# Active_Probe_Proto2.net
KiCad netlist of a schematic drawn in EAGLE
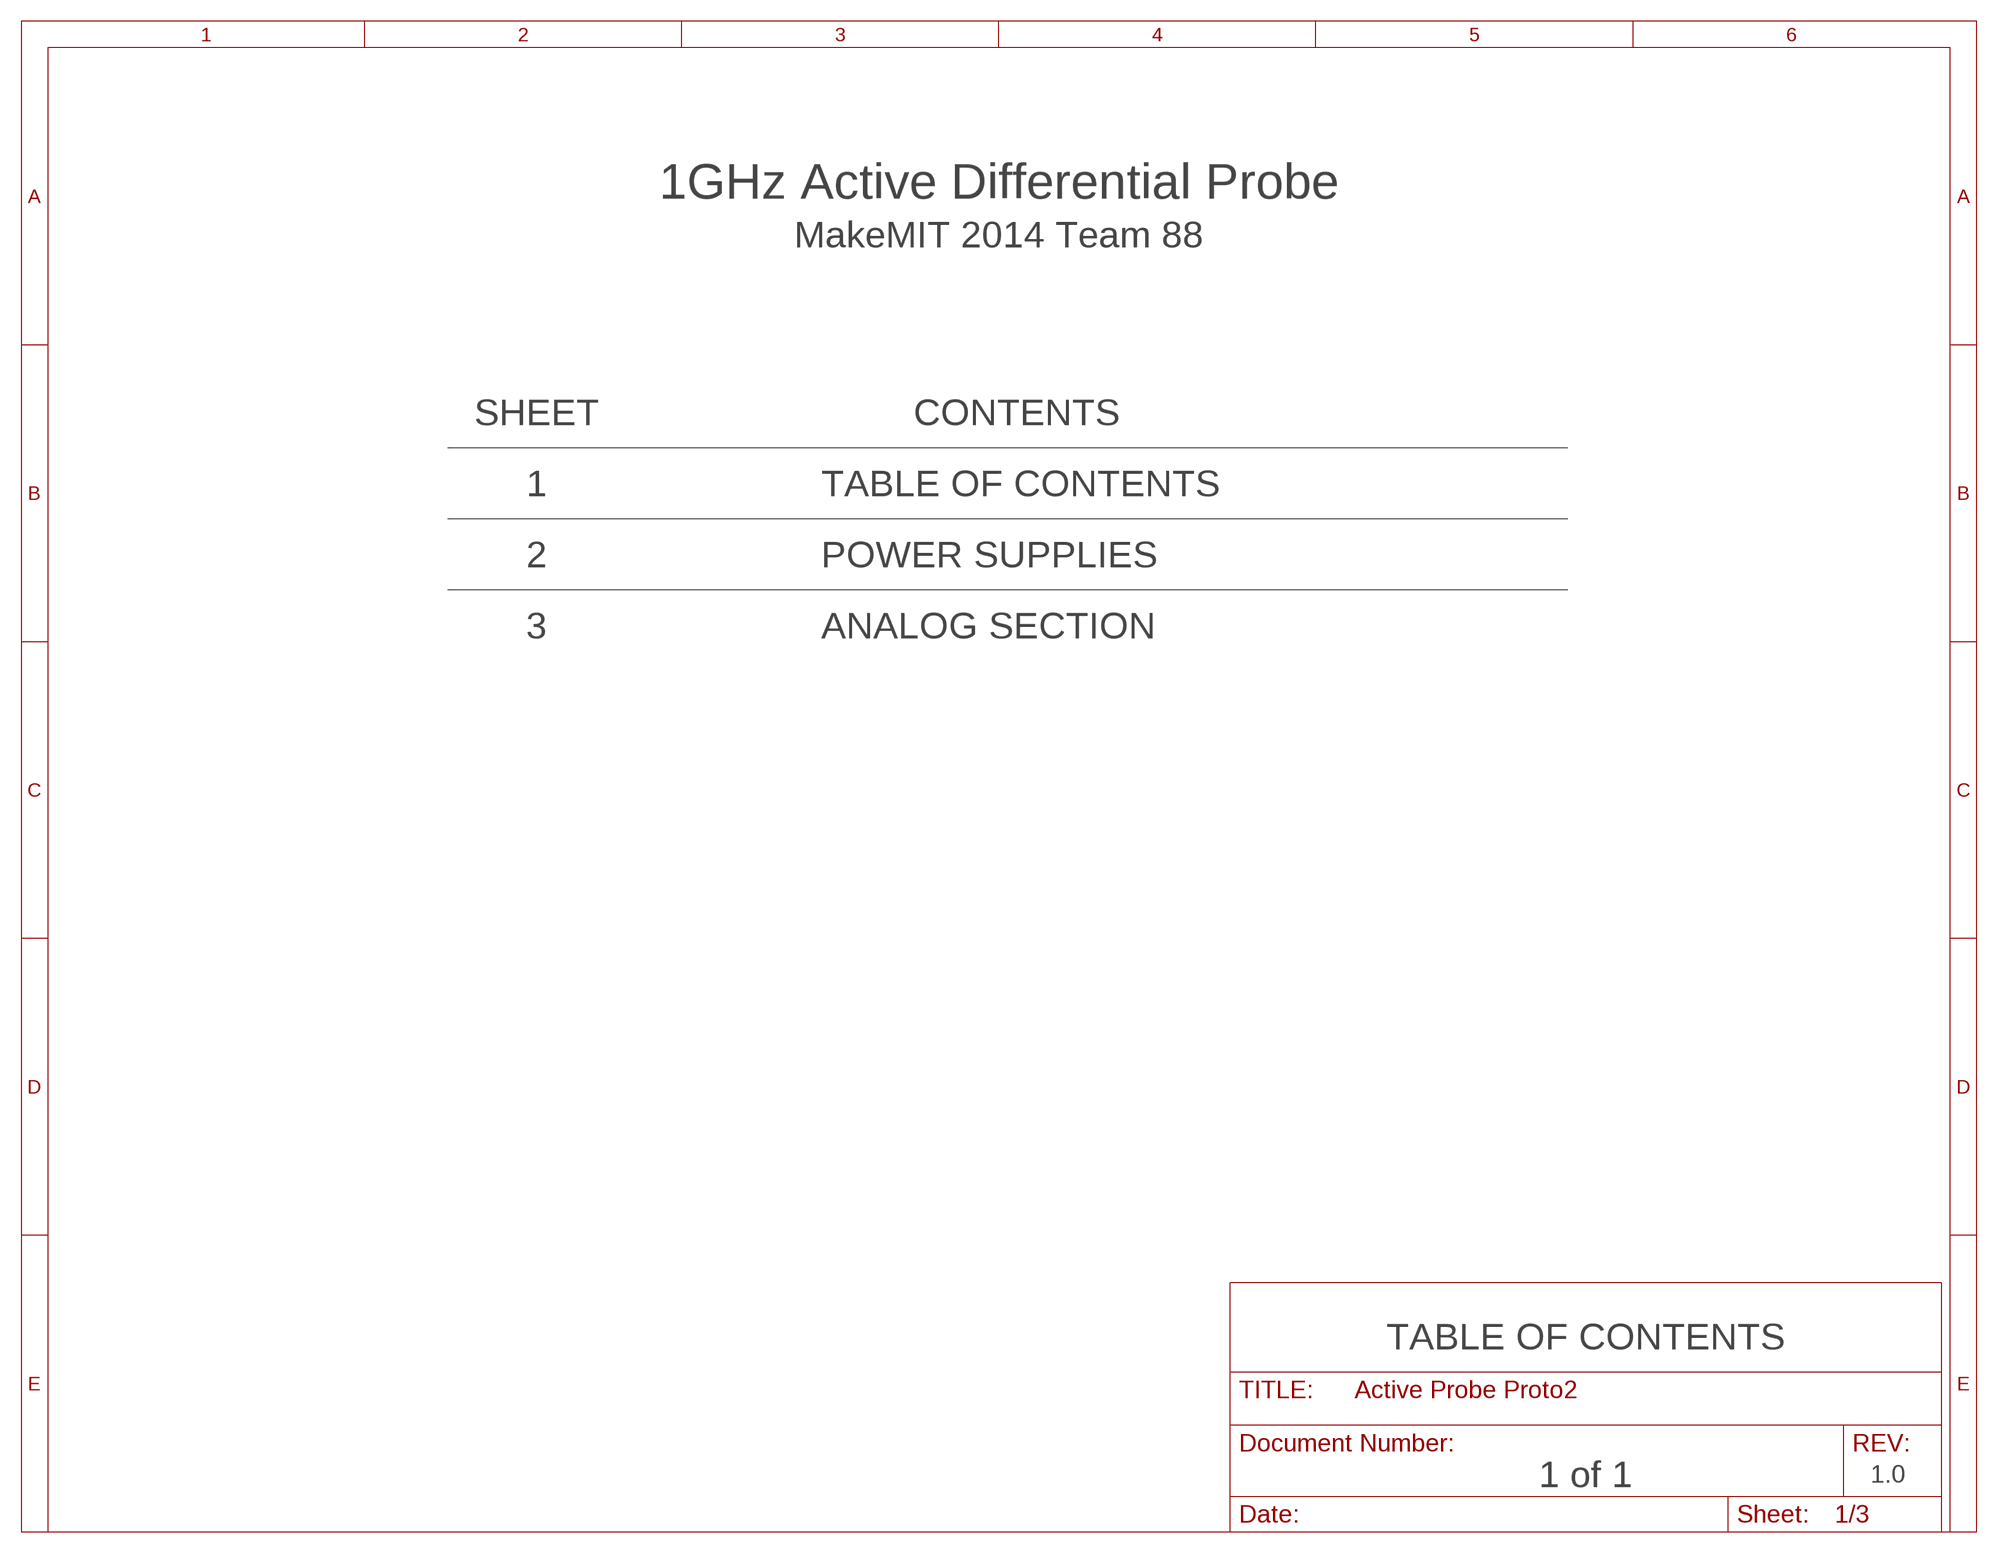
[diagram p0: schematic, sheet 1]
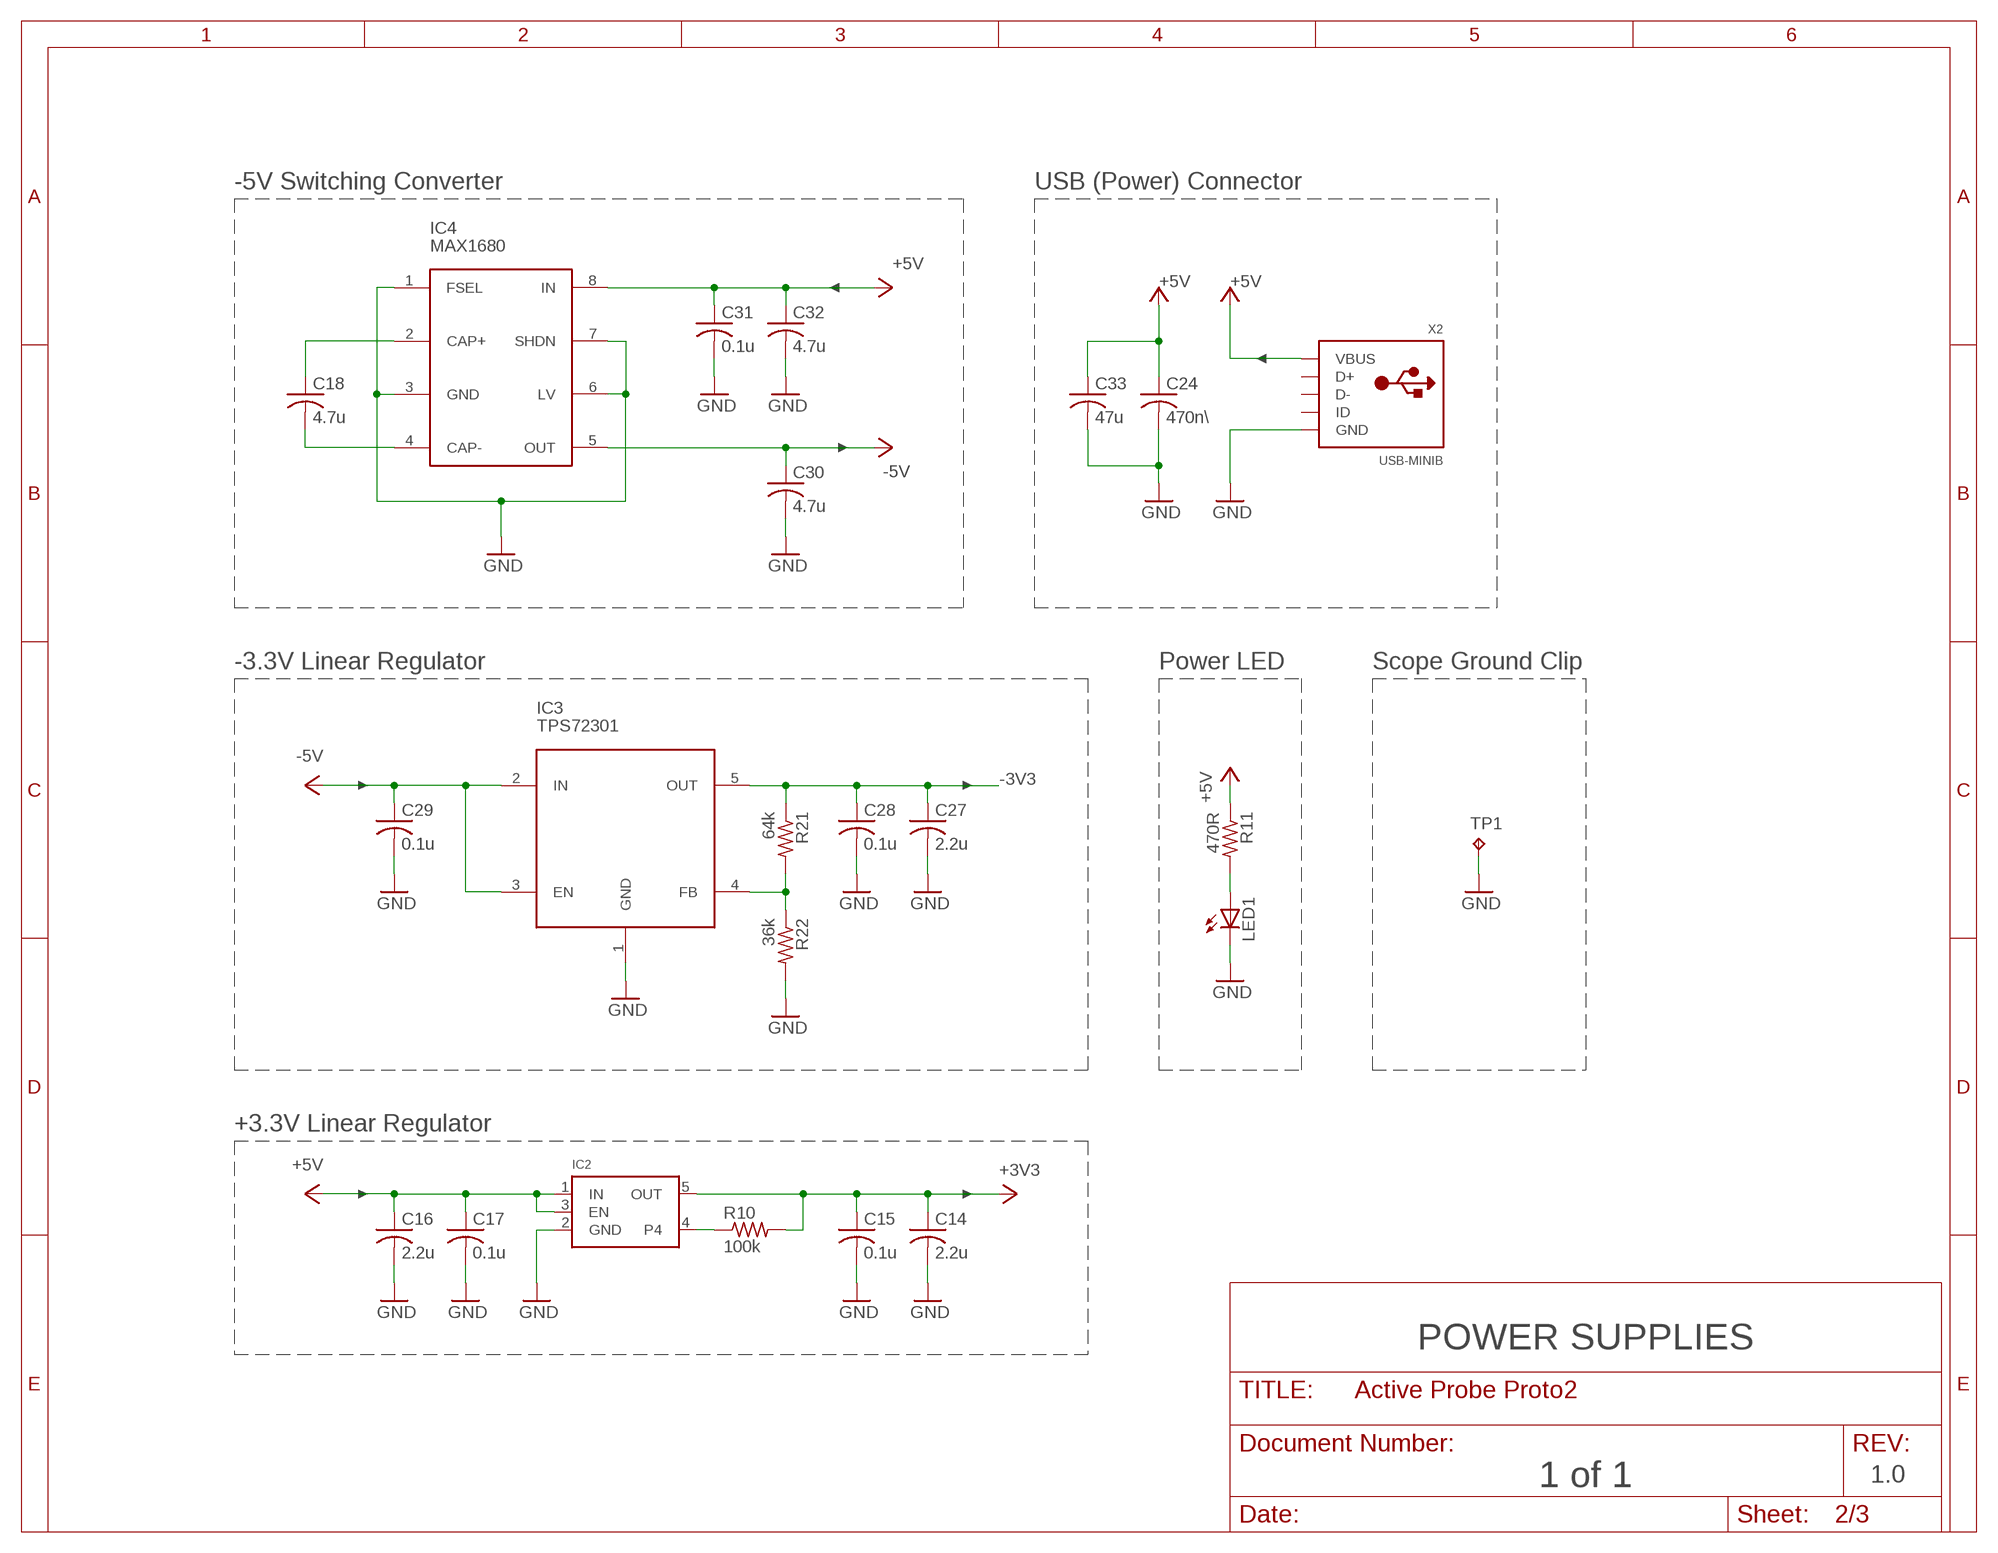
[diagram p1: schematic, sheet 2]
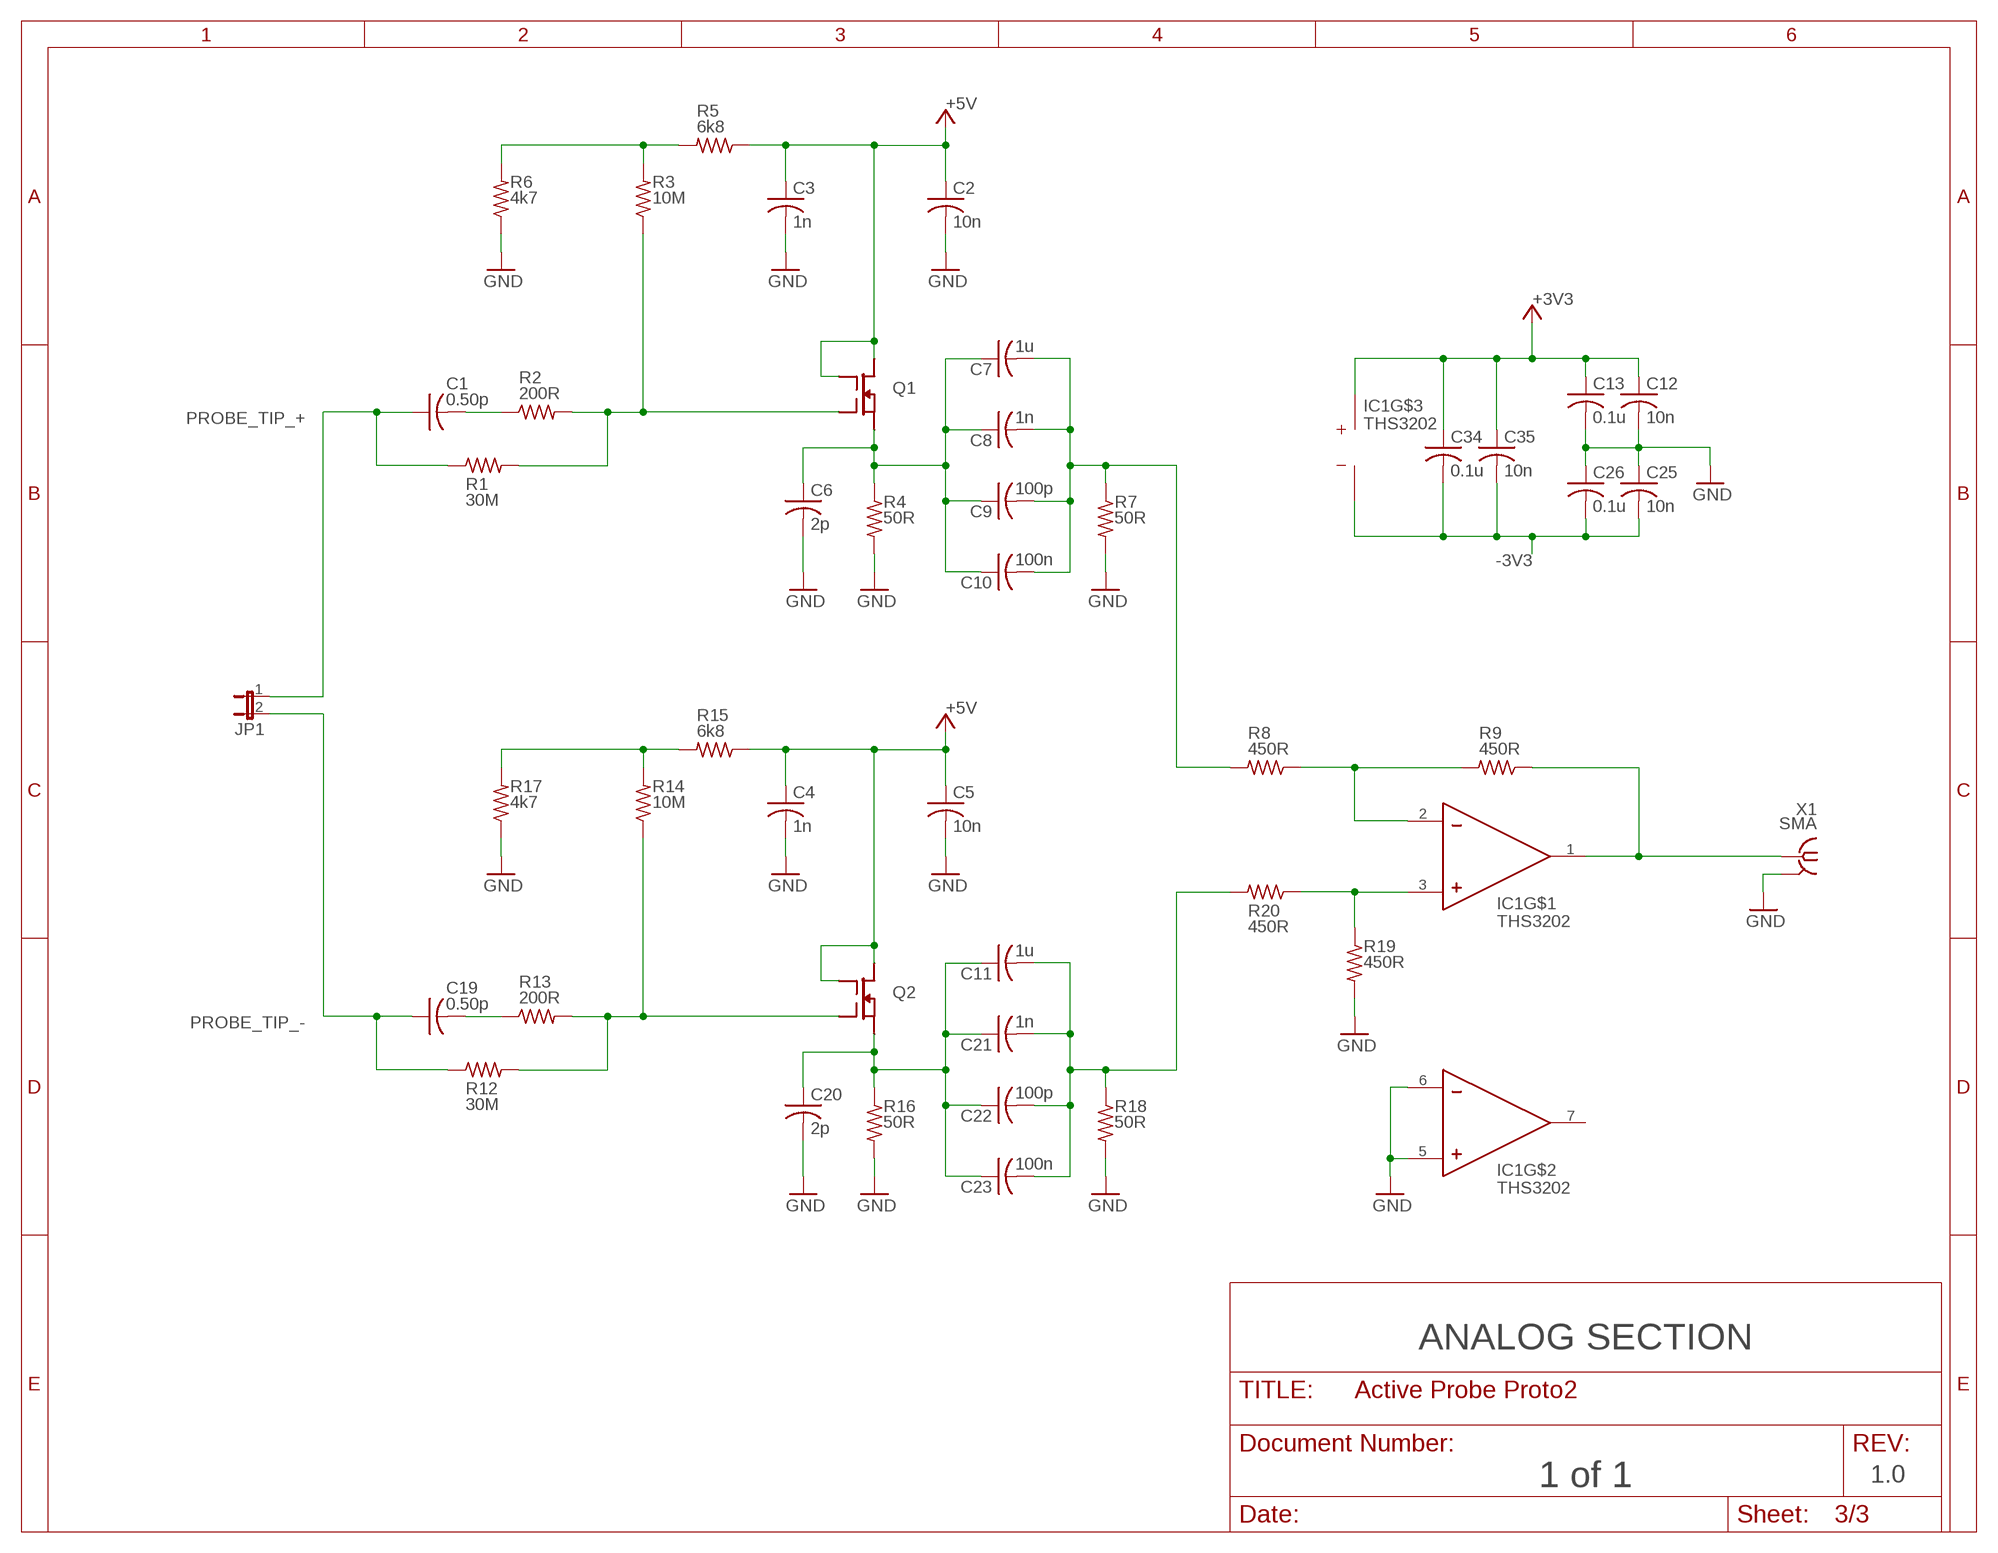
[diagram p2: schematic, sheet 3]

(export (version "E")
  (design (tool "Eeschema 10.0.6"))
  (components
    (comp (ref "C1")
      (value "0.50p")
      (footprint "eagle-import:C0603")
      (libsource (lib "eagle-import") (part "C-USC0603"))
    )
    (comp (ref "C2")
      (value "10n")
      (footprint "eagle-import:C0603")
      (libsource (lib "eagle-import") (part "C-USC0603"))
    )
    (comp (ref "C3")
      (value "1n")
      (footprint "eagle-import:C0603")
      (libsource (lib "eagle-import") (part "C-USC0603"))
    )
    (comp (ref "C4")
      (value "1n")
      (footprint "eagle-import:C0603")
      (libsource (lib "eagle-import") (part "C-USC0603"))
    )
    (comp (ref "C5")
      (value "10n")
      (footprint "eagle-import:C0603")
      (libsource (lib "eagle-import") (part "C-USC0603"))
    )
    (comp (ref "C6")
      (value "2p")
      (footprint "eagle-import:C0603")
      (libsource (lib "eagle-import") (part "C-USC0603"))
    )
    (comp (ref "C7")
      (value "1u")
      (footprint "eagle-import:C0603")
      (libsource (lib "eagle-import") (part "C-USC0603"))
    )
    (comp (ref "C8")
      (value "1n")
      (footprint "eagle-import:C0603")
      (libsource (lib "eagle-import") (part "C-USC0603"))
    )
    (comp (ref "C9")
      (value "100p")
      (footprint "eagle-import:C0603")
      (libsource (lib "eagle-import") (part "C-USC0603"))
    )
    (comp (ref "C10")
      (value "100n")
      (footprint "eagle-import:C0603")
      (libsource (lib "eagle-import") (part "C-USC0603"))
    )
    (comp (ref "C11")
      (value "1u")
      (footprint "eagle-import:C0603")
      (libsource (lib "eagle-import") (part "C-USC0603"))
    )
    (comp (ref "C12")
      (value "10n")
      (footprint "eagle-import:C0603")
      (libsource (lib "eagle-import") (part "C-USC0603"))
    )
    (comp (ref "C13")
      (value "0.1u")
      (footprint "eagle-import:C0603")
      (libsource (lib "eagle-import") (part "C-USC0603"))
    )
    (comp (ref "C19")
      (value "0.50p")
      (footprint "eagle-import:C0603")
      (libsource (lib "eagle-import") (part "C-USC0603"))
    )
    (comp (ref "C20")
      (value "2p")
      (footprint "eagle-import:C0603")
      (libsource (lib "eagle-import") (part "C-USC0603"))
    )
    (comp (ref "C21")
      (value "1n")
      (footprint "eagle-import:C0603")
      (libsource (lib "eagle-import") (part "C-USC0603"))
    )
    (comp (ref "C22")
      (value "100p")
      (footprint "eagle-import:C0603")
      (libsource (lib "eagle-import") (part "C-USC0603"))
    )
    (comp (ref "C23")
      (value "100n")
      (footprint "eagle-import:C0603")
      (libsource (lib "eagle-import") (part "C-USC0603"))
    )
    (comp (ref "C25")
      (value "10n")
      (footprint "eagle-import:C0603")
      (libsource (lib "eagle-import") (part "C-USC0603"))
    )
    (comp (ref "C26")
      (value "0.1u")
      (footprint "eagle-import:C0603")
      (libsource (lib "eagle-import") (part "C-USC0603"))
    )
    (comp (ref "C34")
      (value "0.1u")
      (footprint "eagle-import:C0603")
      (libsource (lib "eagle-import") (part "C-USC0603"))
    )
    (comp (ref "C35")
      (value "10n")
      (footprint "eagle-import:C0603")
      (libsource (lib "eagle-import") (part "C-USC0603"))
    )
    (comp (ref "IC1")
      (value "THS3202")
      (footprint "eagle-import:SOIC8")
      (libsource (lib "eagle-import") (part "THS3202"))
    )
    (comp (ref "JP1")
      (value "HEADER_SIDE_2POS")
      (footprint "eagle-import:HEADER_SIDE_2POS")
      (libsource (lib "eagle-import") (part "HEADER_SIDE_2POS"))
    )
    (comp (ref "Q1")
      (value "BF998")
      (footprint "eagle-import:SOT143B")
      (libsource (lib "eagle-import") (part "BF998"))
    )
    (comp (ref "Q2")
      (value "BF998")
      (footprint "eagle-import:SOT143B")
      (libsource (lib "eagle-import") (part "BF998"))
    )
    (comp (ref "R1")
      (value "30M")
      (footprint "eagle-import:R0603")
      (libsource (lib "eagle-import") (part "R-US_R0603"))
    )
    (comp (ref "R2")
      (value "200R")
      (footprint "eagle-import:R0603")
      (libsource (lib "eagle-import") (part "R-US_R0603"))
    )
    (comp (ref "R3")
      (value "10M")
      (footprint "eagle-import:R0603")
      (libsource (lib "eagle-import") (part "R-US_R0603"))
    )
    (comp (ref "R4")
      (value "50R")
      (footprint "eagle-import:R0603")
      (libsource (lib "eagle-import") (part "R-US_R0603"))
    )
    (comp (ref "R5")
      (value "6k8")
      (footprint "eagle-import:R0603")
      (libsource (lib "eagle-import") (part "R-US_R0603"))
    )
    (comp (ref "R6")
      (value "4k7")
      (footprint "eagle-import:R0603")
      (libsource (lib "eagle-import") (part "R-US_R0603"))
    )
    (comp (ref "R7")
      (value "50R")
      (footprint "eagle-import:R0603")
      (libsource (lib "eagle-import") (part "R-US_R0603"))
    )
    (comp (ref "R8")
      (value "450R")
      (footprint "eagle-import:R0603")
      (libsource (lib "eagle-import") (part "R-US_R0603"))
    )
    (comp (ref "R9")
      (value "450R")
      (footprint "eagle-import:R0603")
      (libsource (lib "eagle-import") (part "R-US_R0603"))
    )
    (comp (ref "R12")
      (value "30M")
      (footprint "eagle-import:R0603")
      (libsource (lib "eagle-import") (part "R-US_R0603"))
    )
    (comp (ref "R13")
      (value "200R")
      (footprint "eagle-import:R0603")
      (libsource (lib "eagle-import") (part "R-US_R0603"))
    )
    (comp (ref "R14")
      (value "10M")
      (footprint "eagle-import:R0603")
      (libsource (lib "eagle-import") (part "R-US_R0603"))
    )
    (comp (ref "R15")
      (value "6k8")
      (footprint "eagle-import:R0603")
      (libsource (lib "eagle-import") (part "R-US_R0603"))
    )
    (comp (ref "R16")
      (value "50R")
      (footprint "eagle-import:R0603")
      (libsource (lib "eagle-import") (part "R-US_R0603"))
    )
    (comp (ref "R17")
      (value "4k7")
      (footprint "eagle-import:R0603")
      (libsource (lib "eagle-import") (part "R-US_R0603"))
    )
    (comp (ref "R18")
      (value "50R")
      (footprint "eagle-import:R0603")
      (libsource (lib "eagle-import") (part "R-US_R0603"))
    )
    (comp (ref "R19")
      (value "450R")
      (footprint "eagle-import:R0603")
      (libsource (lib "eagle-import") (part "R-US_R0603"))
    )
    (comp (ref "R20")
      (value "450R")
      (footprint "eagle-import:R0603")
      (libsource (lib "eagle-import") (part "R-US_R0603"))
    )
    (comp (ref "X1")
      (value "SMA")
      (footprint "eagle-import:J502-ND-142-0701-801_806")
      (fields (field (name "MF") "JOHNSON COMPONENTS") (field (name "MPN") "142-0701-801"))
      (libsource (lib "eagle-import") (part "SMA-142-0701-801/806"))
    )
    (comp (ref "C14")
      (value "2.2u")
      (footprint "eagle-import:C0603")
      (libsource (lib "eagle-import") (part "C-USC0603"))
    )
    (comp (ref "C15")
      (value "0.1u")
      (footprint "eagle-import:C0603")
      (libsource (lib "eagle-import") (part "C-USC0603"))
    )
    (comp (ref "C16")
      (value "2.2u")
      (footprint "eagle-import:C0603")
      (libsource (lib "eagle-import") (part "C-USC0603"))
    )
    (comp (ref "C17")
      (value "0.1u")
      (footprint "eagle-import:C0603")
      (libsource (lib "eagle-import") (part "C-USC0603"))
    )
    (comp (ref "C18")
      (value "4.7u")
      (footprint "eagle-import:C0603")
      (libsource (lib "eagle-import") (part "C-USC0603"))
    )
    (comp (ref "C24")
      (value "470n\\")
      (footprint "eagle-import:C0603")
      (libsource (lib "eagle-import") (part "C-USC0603"))
    )
    (comp (ref "C27")
      (value "2.2u")
      (footprint "eagle-import:C0603")
      (libsource (lib "eagle-import") (part "C-USC0603"))
    )
    (comp (ref "C28")
      (value "0.1u")
      (footprint "eagle-import:C0603")
      (libsource (lib "eagle-import") (part "C-USC0603"))
    )
    (comp (ref "C29")
      (value "0.1u")
      (footprint "eagle-import:C0603")
      (libsource (lib "eagle-import") (part "C-USC0603"))
    )
    (comp (ref "C30")
      (value "4.7u")
      (footprint "eagle-import:C0603")
      (libsource (lib "eagle-import") (part "C-USC0603"))
    )
    (comp (ref "C31")
      (value "0.1u")
      (footprint "eagle-import:C0603")
      (libsource (lib "eagle-import") (part "C-USC0603"))
    )
    (comp (ref "C32")
      (value "4.7u")
      (footprint "eagle-import:C0603")
      (libsource (lib "eagle-import") (part "C-USC0603"))
    )
    (comp (ref "C33")
      (value "47u")
      (footprint "eagle-import:C1206")
      (libsource (lib "eagle-import") (part "C-USC1206"))
    )
    (comp (ref "IC2")
      (value "VREG_SOT23-5")
      (footprint "eagle-import:SOT23-5")
      (libsource (lib "eagle-import") (part "VREG_SOT23-5"))
    )
    (comp (ref "IC3")
      (value "TPS72301")
      (footprint "eagle-import:SOT23-5L")
      (libsource (lib "eagle-import") (part "TPS72301"))
    )
    (comp (ref "IC4")
      (value "MAX1680")
      (footprint "eagle-import:SO8")
      (libsource (lib "eagle-import") (part "MAX1680/1"))
    )
    (comp (ref "LED1")
      (value "LED3MM")
      (footprint "eagle-import:LED3MM")
      (libsource (lib "eagle-import") (part "LED3MM"))
    )
    (comp (ref "R10")
      (value "100k")
      (footprint "eagle-import:R0603")
      (libsource (lib "eagle-import") (part "R-US_R0603"))
    )
    (comp (ref "R11")
      (value "470R")
      (footprint "eagle-import:R0805")
      (libsource (lib "eagle-import") (part "R-US_R0805"))
    )
    (comp (ref "R21")
      (value "64k")
      (footprint "eagle-import:R0603")
      (libsource (lib "eagle-import") (part "R-US_R0603"))
    )
    (comp (ref "R22")
      (value "36k")
      (footprint "eagle-import:R0603")
      (libsource (lib "eagle-import") (part "R-US_R0603"))
    )
    (comp (ref "TP1")
      (value "TPTP20SQ")
      (footprint "eagle-import:TP20SQ")
      (libsource (lib "eagle-import") (part "TPTP20SQ"))
    )
    (comp (ref "X2")
      (value "USB-MINIB")
      (footprint "eagle-import:USB-MINIB")
      (libsource (lib "eagle-import") (part "USBMINIB"))
    )
  )
  (nets
    (net (code "1") (name "+3V3") (class "Default")
      (node (ref "C12") (pin "1") (pinfunction "1_1") (pintype "passive"))
      (node (ref "C13") (pin "1") (pinfunction "1_1") (pintype "passive"))
      (node (ref "C14") (pin "1") (pinfunction "1_1") (pintype "passive"))
      (node (ref "C15") (pin "1") (pinfunction "1_1") (pintype "passive"))
      (node (ref "C34") (pin "1") (pinfunction "1_1") (pintype "passive"))
      (node (ref "C35") (pin "1") (pinfunction "1_1") (pintype "passive"))
      (node (ref "IC1") (pin "8") (pinfunction "VCC_8") (pintype "power_in"))
      (node (ref "IC2") (pin "5") (pinfunction "OUT_5") (pintype "bidirectional"))
      (node (ref "R10") (pin "2") (pinfunction "2_2") (pintype "passive"))
    )
    (net (code "2") (name "+5V") (class "Default")
      (node (ref "C16") (pin "1") (pinfunction "1_1") (pintype "passive"))
      (node (ref "C17") (pin "1") (pinfunction "1_1") (pintype "passive"))
      (node (ref "C2") (pin "1") (pinfunction "1_1") (pintype "passive"))
      (node (ref "C24") (pin "1") (pinfunction "1_1") (pintype "passive"))
      (node (ref "C3") (pin "1") (pinfunction "1_1") (pintype "passive"))
      (node (ref "C31") (pin "1") (pinfunction "1_1") (pintype "passive"))
      (node (ref "C32") (pin "1") (pinfunction "1_1") (pintype "passive"))
      (node (ref "C33") (pin "1") (pinfunction "1_1") (pintype "passive"))
      (node (ref "C4") (pin "1") (pinfunction "1_1") (pintype "passive"))
      (node (ref "C5") (pin "1") (pinfunction "1_1") (pintype "passive"))
      (node (ref "IC2") (pin "1") (pinfunction "IN_1") (pintype "bidirectional"))
      (node (ref "IC2") (pin "3") (pinfunction "EN_3") (pintype "bidirectional"))
      (node (ref "IC4") (pin "8") (pinfunction "IN_8") (pintype "bidirectional"))
      (node (ref "Q1") (pin "2") (pinfunction "D_2") (pintype "bidirectional"))
      (node (ref "Q1") (pin "3") (pinfunction "G2_3") (pintype "bidirectional"))
      (node (ref "Q2") (pin "2") (pinfunction "D_2") (pintype "bidirectional"))
      (node (ref "Q2") (pin "3") (pinfunction "G2_3") (pintype "bidirectional"))
      (node (ref "R11") (pin "1") (pinfunction "1_1") (pintype "passive"))
      (node (ref "R15") (pin "1") (pinfunction "1_1") (pintype "passive"))
      (node (ref "R5") (pin "1") (pinfunction "1_1") (pintype "passive"))
      (node (ref "X2") (pin "VBUS") (pinfunction "VBUS_VBUS") (pintype "power_in"))
    )
    (net (code "3") (name "-3V3") (class "Default")
      (node (ref "C25") (pin "2") (pinfunction "2_2") (pintype "passive"))
      (node (ref "C26") (pin "2") (pinfunction "2_2") (pintype "passive"))
      (node (ref "C27") (pin "1") (pinfunction "1_1") (pintype "passive"))
      (node (ref "C28") (pin "1") (pinfunction "1_1") (pintype "passive"))
      (node (ref "C34") (pin "2") (pinfunction "2_2") (pintype "passive"))
      (node (ref "C35") (pin "2") (pinfunction "2_2") (pintype "passive"))
      (node (ref "IC1") (pin "4") (pinfunction "GND_4") (pintype "power_in"))
      (node (ref "IC3") (pin "5") (pinfunction "OUT_5") (pintype "bidirectional"))
      (node (ref "R21") (pin "1") (pinfunction "1_1") (pintype "passive"))
    )
    (net (code "4") (name "-5V") (class "Default")
      (node (ref "C29") (pin "1") (pinfunction "1_1") (pintype "passive"))
      (node (ref "C30") (pin "1") (pinfunction "1_1") (pintype "passive"))
      (node (ref "IC3") (pin "2") (pinfunction "IN_2") (pintype "bidirectional"))
      (node (ref "IC3") (pin "3") (pinfunction "EN_3") (pintype "bidirectional"))
      (node (ref "IC4") (pin "5") (pinfunction "OUT_5") (pintype "bidirectional"))
    )
    (net (code "5") (name "GND") (class "Default")
      (node (ref "C12") (pin "2") (pinfunction "2_2") (pintype "passive"))
      (node (ref "C13") (pin "2") (pinfunction "2_2") (pintype "passive"))
      (node (ref "C14") (pin "2") (pinfunction "2_2") (pintype "passive"))
      (node (ref "C15") (pin "2") (pinfunction "2_2") (pintype "passive"))
      (node (ref "C16") (pin "2") (pinfunction "2_2") (pintype "passive"))
      (node (ref "C17") (pin "2") (pinfunction "2_2") (pintype "passive"))
      (node (ref "C2") (pin "2") (pinfunction "2_2") (pintype "passive"))
      (node (ref "C20") (pin "2") (pinfunction "2_2") (pintype "passive"))
      (node (ref "C24") (pin "2") (pinfunction "2_2") (pintype "passive"))
      (node (ref "C25") (pin "1") (pinfunction "1_1") (pintype "passive"))
      (node (ref "C26") (pin "1") (pinfunction "1_1") (pintype "passive"))
      (node (ref "C27") (pin "2") (pinfunction "2_2") (pintype "passive"))
      (node (ref "C28") (pin "2") (pinfunction "2_2") (pintype "passive"))
      (node (ref "C29") (pin "2") (pinfunction "2_2") (pintype "passive"))
      (node (ref "C3") (pin "2") (pinfunction "2_2") (pintype "passive"))
      (node (ref "C30") (pin "2") (pinfunction "2_2") (pintype "passive"))
      (node (ref "C31") (pin "2") (pinfunction "2_2") (pintype "passive"))
      (node (ref "C32") (pin "2") (pinfunction "2_2") (pintype "passive"))
      (node (ref "C33") (pin "2") (pinfunction "2_2") (pintype "passive"))
      (node (ref "C4") (pin "2") (pinfunction "2_2") (pintype "passive"))
      (node (ref "C5") (pin "2") (pinfunction "2_2") (pintype "passive"))
      (node (ref "C6") (pin "2") (pinfunction "2_2") (pintype "passive"))
      (node (ref "IC1") (pin "5") (pinfunction "IN+_5") (pintype "input"))
      (node (ref "IC1") (pin "6") (pinfunction "IN-_6") (pintype "input"))
      (node (ref "IC2") (pin "2") (pinfunction "GND_2") (pintype "bidirectional"))
      (node (ref "IC3") (pin "1") (pinfunction "GND_1") (pintype "bidirectional"))
      (node (ref "IC4") (pin "1") (pinfunction "FSEL_1") (pintype "bidirectional"))
      (node (ref "IC4") (pin "3") (pinfunction "GND_3") (pintype "bidirectional"))
      (node (ref "IC4") (pin "6") (pinfunction "LV_6") (pintype "bidirectional"))
      (node (ref "IC4") (pin "7") (pinfunction "SHDN_7") (pintype "bidirectional"))
      (node (ref "LED1") (pin "K") (pinfunction "C_K") (pintype "passive"))
      (node (ref "R16") (pin "2") (pinfunction "2_2") (pintype "passive"))
      (node (ref "R17") (pin "1") (pinfunction "1_1") (pintype "passive"))
      (node (ref "R18") (pin "2") (pinfunction "2_2") (pintype "passive"))
      (node (ref "R19") (pin "2") (pinfunction "2_2") (pintype "passive"))
      (node (ref "R22") (pin "2") (pinfunction "2_2") (pintype "passive"))
      (node (ref "R4") (pin "2") (pinfunction "2_2") (pintype "passive"))
      (node (ref "R6") (pin "1") (pinfunction "1_1") (pintype "passive"))
      (node (ref "R7") (pin "2") (pinfunction "2_2") (pintype "passive"))
      (node (ref "TP1") (pin "TP") (pinfunction "TP_TP") (pintype "input"))
      (node (ref "X1") (pin "G@1") (pinfunction "GND_G@1") (pintype "power_in"))
      (node (ref "X2") (pin "GND") (pinfunction "GND_GND") (pintype "power_in"))
    )
    (net (code "6") (name "Net-(C1-Pad2)") (class "Default")
      (node (ref "C1") (pin "2") (pinfunction "2_2") (pintype "passive"))
      (node (ref "R2") (pin "1") (pinfunction "1_1") (pintype "passive"))
    )
    (net (code "7") (name "Net-(C10-Pad2)") (class "Default")
      (node (ref "C10") (pin "2") (pinfunction "2_2") (pintype "passive"))
      (node (ref "C7") (pin "2") (pinfunction "2_2") (pintype "passive"))
      (node (ref "C8") (pin "2") (pinfunction "2_2") (pintype "passive"))
      (node (ref "C9") (pin "2") (pinfunction "2_2") (pintype "passive"))
      (node (ref "R7") (pin "1") (pinfunction "1_1") (pintype "passive"))
      (node (ref "R8") (pin "2") (pinfunction "2_2") (pintype "passive"))
    )
    (net (code "8") (name "Net-(C11-Pad2)") (class "Default")
      (node (ref "C11") (pin "2") (pinfunction "2_2") (pintype "passive"))
      (node (ref "C21") (pin "2") (pinfunction "2_2") (pintype "passive"))
      (node (ref "C22") (pin "2") (pinfunction "2_2") (pintype "passive"))
      (node (ref "C23") (pin "2") (pinfunction "2_2") (pintype "passive"))
      (node (ref "R18") (pin "1") (pinfunction "1_1") (pintype "passive"))
      (node (ref "R20") (pin "2") (pinfunction "2_2") (pintype "passive"))
    )
    (net (code "9") (name "Net-(C19-Pad2)") (class "Default")
      (node (ref "C19") (pin "2") (pinfunction "2_2") (pintype "passive"))
      (node (ref "R13") (pin "1") (pinfunction "1_1") (pintype "passive"))
    )
    (net (code "10") (name "Net-(IC1A-IN+)") (class "Default")
      (node (ref "IC1") (pin "3") (pinfunction "IN+_3") (pintype "input"))
      (node (ref "R19") (pin "1") (pinfunction "1_1") (pintype "passive"))
      (node (ref "R20") (pin "1") (pinfunction "1_1") (pintype "passive"))
    )
    (net (code "11") (name "Net-(IC1A-IN-)") (class "Default")
      (node (ref "IC1") (pin "2") (pinfunction "IN-_2") (pintype "input"))
      (node (ref "R8") (pin "1") (pinfunction "1_1") (pintype "passive"))
      (node (ref "R9") (pin "2") (pinfunction "2_2") (pintype "passive"))
    )
    (net (code "12") (name "Net-(IC1A-OUT)") (class "Default")
      (node (ref "IC1") (pin "1") (pinfunction "OUT_1") (pintype "output"))
      (node (ref "R9") (pin "1") (pinfunction "1_1") (pintype "passive"))
      (node (ref "X1") (pin "1") (pinfunction "1_1") (pintype "passive"))
    )
    (net (code "13") (name "Net-(IC2-P4)") (class "Default")
      (node (ref "IC2") (pin "4") (pinfunction "P4_4") (pintype "bidirectional"))
      (node (ref "R10") (pin "1") (pinfunction "1_1") (pintype "passive"))
    )
    (net (code "14") (name "Net-(IC3-FB)") (class "Default")
      (node (ref "IC3") (pin "4") (pinfunction "FB_4") (pintype "bidirectional"))
      (node (ref "R21") (pin "2") (pinfunction "2_2") (pintype "passive"))
      (node (ref "R22") (pin "1") (pinfunction "1_1") (pintype "passive"))
    )
    (net (code "15") (name "Net-(IC4-CAP+)") (class "Default")
      (node (ref "C18") (pin "1") (pinfunction "1_1") (pintype "passive"))
      (node (ref "IC4") (pin "2") (pinfunction "CAP+_2") (pintype "bidirectional"))
    )
    (net (code "16") (name "Net-(IC4-CAP-)") (class "Default")
      (node (ref "C18") (pin "2") (pinfunction "2_2") (pintype "passive"))
      (node (ref "IC4") (pin "4") (pinfunction "CAP-_4") (pintype "bidirectional"))
    )
    (net (code "17") (name "Net-(LED1-PadA)") (class "Default")
      (node (ref "LED1") (pin "A") (pinfunction "A_A") (pintype "passive"))
      (node (ref "R11") (pin "2") (pinfunction "2_2") (pintype "passive"))
    )
    (net (code "18") (name "Net-(Q1-G1)") (class "Default")
      (node (ref "Q1") (pin "4") (pinfunction "G1_4") (pintype "bidirectional"))
      (node (ref "R1") (pin "2") (pinfunction "2_2") (pintype "passive"))
      (node (ref "R2") (pin "2") (pinfunction "2_2") (pintype "passive"))
      (node (ref "R3") (pin "1") (pinfunction "1_1") (pintype "passive"))
    )
    (net (code "19") (name "Net-(Q1-S)") (class "Default")
      (node (ref "C10") (pin "1") (pinfunction "1_1") (pintype "passive"))
      (node (ref "C6") (pin "1") (pinfunction "1_1") (pintype "passive"))
      (node (ref "C7") (pin "1") (pinfunction "1_1") (pintype "passive"))
      (node (ref "C8") (pin "1") (pinfunction "1_1") (pintype "passive"))
      (node (ref "C9") (pin "1") (pinfunction "1_1") (pintype "passive"))
      (node (ref "Q1") (pin "1") (pinfunction "S_1") (pintype "bidirectional"))
      (node (ref "R4") (pin "1") (pinfunction "1_1") (pintype "passive"))
    )
    (net (code "20") (name "Net-(Q2-G1)") (class "Default")
      (node (ref "Q2") (pin "4") (pinfunction "G1_4") (pintype "bidirectional"))
      (node (ref "R12") (pin "2") (pinfunction "2_2") (pintype "passive"))
      (node (ref "R13") (pin "2") (pinfunction "2_2") (pintype "passive"))
      (node (ref "R14") (pin "1") (pinfunction "1_1") (pintype "passive"))
    )
    (net (code "21") (name "Net-(Q2-S)") (class "Default")
      (node (ref "C11") (pin "1") (pinfunction "1_1") (pintype "passive"))
      (node (ref "C20") (pin "1") (pinfunction "1_1") (pintype "passive"))
      (node (ref "C21") (pin "1") (pinfunction "1_1") (pintype "passive"))
      (node (ref "C22") (pin "1") (pinfunction "1_1") (pintype "passive"))
      (node (ref "C23") (pin "1") (pinfunction "1_1") (pintype "passive"))
      (node (ref "Q2") (pin "1") (pinfunction "S_1") (pintype "bidirectional"))
      (node (ref "R16") (pin "1") (pinfunction "1_1") (pintype "passive"))
    )
    (net (code "22") (name "Net-(R3-Pad2)") (class "Default")
      (node (ref "R3") (pin "2") (pinfunction "2_2") (pintype "passive"))
      (node (ref "R5") (pin "2") (pinfunction "2_2") (pintype "passive"))
      (node (ref "R6") (pin "2") (pinfunction "2_2") (pintype "passive"))
    )
    (net (code "23") (name "Net-(R14-Pad2)") (class "Default")
      (node (ref "R14") (pin "2") (pinfunction "2_2") (pintype "passive"))
      (node (ref "R15") (pin "2") (pinfunction "2_2") (pintype "passive"))
      (node (ref "R17") (pin "2") (pinfunction "2_2") (pintype "passive"))
    )
    (net (code "24") (name "PROBE_TIP_+") (class "Default")
      (node (ref "C1") (pin "1") (pinfunction "1_1") (pintype "passive"))
      (node (ref "JP1") (pin "1") (pinfunction "1_1") (pintype "passive"))
      (node (ref "R1") (pin "1") (pinfunction "1_1") (pintype "passive"))
    )
    (net (code "25") (name "PROBE_TIP_-") (class "Default")
      (node (ref "C19") (pin "1") (pinfunction "1_1") (pintype "passive"))
      (node (ref "JP1") (pin "2") (pinfunction "2_2") (pintype "passive"))
      (node (ref "R12") (pin "1") (pinfunction "1_1") (pintype "passive"))
    )
    (net (code "26") (name "unconnected-(IC1B-OUT-Pad7)") (class "Default")
      (node (ref "IC1") (pin "7") (pinfunction "OUT_7") (pintype "output"))
    )
    (net (code "27") (name "unconnected-(X2-PadD+)") (class "Default")
      (node (ref "X2") (pin "D+") (pinfunction "D+_D+") (pintype "bidirectional"))
    )
    (net (code "28") (name "unconnected-(X2-PadD-)") (class "Default")
      (node (ref "X2") (pin "D-") (pinfunction "D-_D-") (pintype "bidirectional"))
    )
    (net (code "29") (name "unconnected-(X2-PadID)") (class "Default")
      (node (ref "X2") (pin "ID") (pinfunction "ID_ID") (pintype "bidirectional"))
    )
  )
)
